# Sheet2.net
KiCad netlist of a schematic drawn in Altium Designer
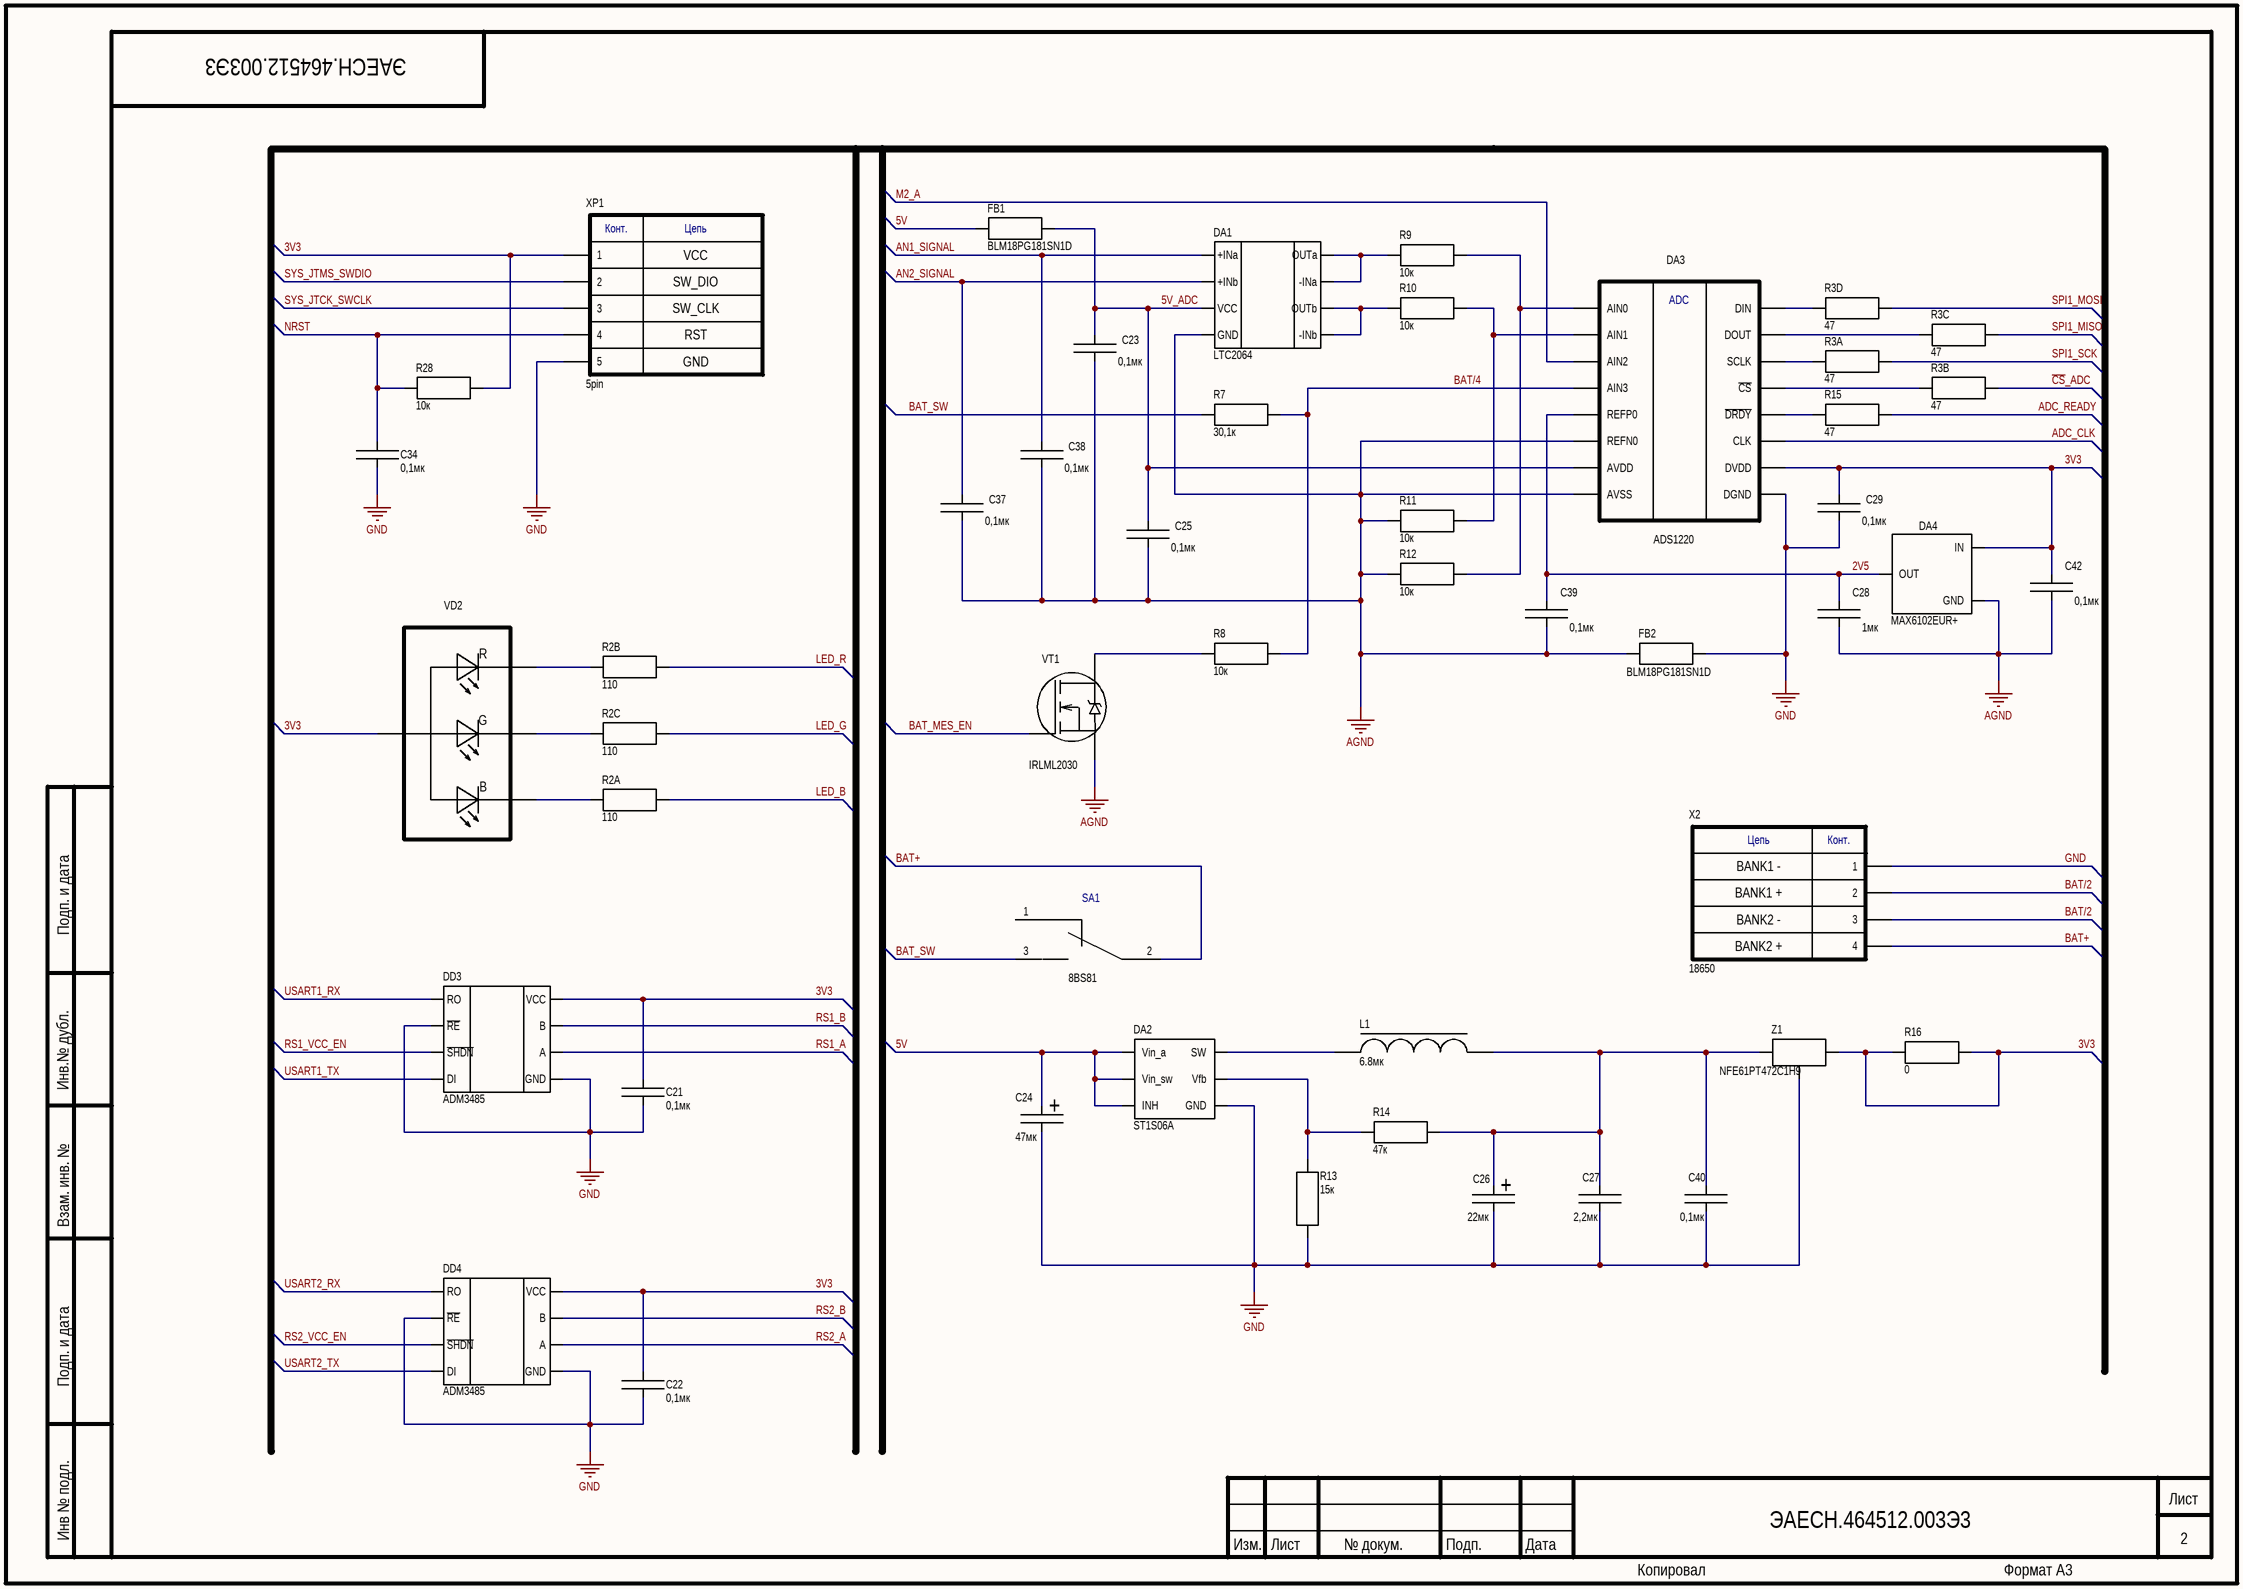
[diagram p0: Sheet2.SchDoc]

(export (version "E")
  (design (tool "Eeschema 10.0.6"))
  (components
    (comp (ref "C21")
      (value "0,1мк")
      (footprint "С0603")
      (fields (field (name "Comment") "C"))
      (libsource (lib "Schlib1") (part "C"))
    )
    (comp (ref "C22")
      (value "0,1мк")
      (footprint "С0603")
      (fields (field (name "Comment") "C"))
      (libsource (lib "Schlib1") (part "C"))
    )
    (comp (ref "C23")
      (value "0,1мк")
      (footprint "С0603")
      (fields (field (name "Comment") "C"))
      (libsource (lib "Schlib1") (part "C"))
    )
    (comp (ref "C24")
      (value "47мк")
      (footprint "CASE B")
      (fields (field (name "Comment") "C_el"))
      (libsource (lib "Schlib1") (part "C_el"))
    )
    (comp (ref "C25")
      (value "0,1мк")
      (footprint "С0603")
      (fields (field (name "Comment") "C"))
      (libsource (lib "Schlib1") (part "C"))
    )
    (comp (ref "C26")
      (value "22мк")
      (footprint "Case A")
      (fields (field (name "Comment") "C_el"))
      (libsource (lib "Schlib1") (part "C_el"))
    )
    (comp (ref "C27")
      (value "2,2мк")
      (footprint "С0603")
      (fields (field (name "Comment") "C"))
      (libsource (lib "Schlib1") (part "C"))
    )
    (comp (ref "C28")
      (value "1мк")
      (footprint "С0603")
      (fields (field (name "Comment") "C"))
      (libsource (lib "Schlib1") (part "C"))
    )
    (comp (ref "C29")
      (value "0,1мк")
      (footprint "С0603")
      (fields (field (name "Comment") "C"))
      (libsource (lib "Schlib1") (part "C"))
    )
    (comp (ref "C34")
      (value "0,1мк")
      (footprint "С0603")
      (fields (field (name "Comment") "C"))
      (libsource (lib "Schlib1") (part "C"))
    )
    (comp (ref "C37")
      (value "0,1мк")
      (footprint "С0603")
      (fields (field (name "Comment") "C"))
      (libsource (lib "Schlib1") (part "C"))
    )
    (comp (ref "C38")
      (value "0,1мк")
      (footprint "С0603")
      (fields (field (name "Comment") "C"))
      (libsource (lib "Schlib1") (part "C"))
    )
    (comp (ref "C39")
      (value "0,1мк")
      (footprint "С0603")
      (fields (field (name "Comment") "C"))
      (libsource (lib "Schlib1") (part "C"))
    )
    (comp (ref "C40")
      (value "0,1мк")
      (footprint "С0603")
      (fields (field (name "Comment") "C"))
      (libsource (lib "Schlib1") (part "C"))
    )
    (comp (ref "C42")
      (value "0,1мк")
      (footprint "С0603")
      (fields (field (name "Comment") "C"))
      (libsource (lib "Schlib1") (part "C"))
    )
    (comp (ref "DA1") (value "LTC2064") (footprint "MSOP8") (libsource (lib "Schlib1") (part "LTC2064")))
    (comp (ref "DA2") (value "ST1S06A") (footprint "DFN6") (libsource (lib "Schlib1") (part "ST1S06A")))
    (comp (ref "DA3") (value "ADS1220") (footprint "TSSOP-16") (libsource (lib "Schlib1") (part "ADC1220")))
    (comp (ref "DA4")
      (value "MAX6102EUR+")
      (footprint "SOT-23")
      (libsource (lib "Schlib1") (part "MAX6102EUR+"))
    )
    (comp (ref "DD3")
      (value "ADM3485")
      (footprint "SOIC8")
      (description "RS485")
      (libsource (lib "Schlib1") (part "MAX13487"))
    )
    (comp (ref "DD4")
      (value "ADM3485")
      (footprint "SOIC8")
      (description "RS485")
      (libsource (lib "Schlib1") (part "MAX13487"))
    )
    (comp (ref "FB1") (value "BLM18PG181SN1D") (footprint "R0603") (libsource (lib "Schlib1") (part "R")))
    (comp (ref "FB2") (value "BLM18PG181SN1D") (footprint "R0603") (libsource (lib "Schlib1") (part "R")))
    (comp (ref "L1") (value "6.8мк") (footprint "Ind_6.5x6.5") (libsource (lib "Schlib1") (part "L")))
    (comp (ref "R2")
      (value "110")
      (footprint "CAT16")
      (fields (field (name "Comment") "RES_4"))
      (libsource (lib "Schlib1") (part "RES_4"))
    )
    (comp (ref "R3")
      (value "47")
      (footprint "CAT16")
      (fields (field (name "Comment") "RES_4"))
      (libsource (lib "Schlib1") (part "RES_4"))
    )
    (comp (ref "R7")
      (value "30,1к")
      (footprint "R0603")
      (fields (field (name "Comment") "R"))
      (libsource (lib "Schlib1") (part "R"))
    )
    (comp (ref "R8")
      (value "10к")
      (footprint "R0603")
      (fields (field (name "Comment") "R"))
      (libsource (lib "Schlib1") (part "R"))
    )
    (comp (ref "R9")
      (value "10к")
      (footprint "R0603")
      (fields (field (name "Comment") "R"))
      (libsource (lib "Schlib1") (part "R"))
    )
    (comp (ref "R10")
      (value "10к")
      (footprint "R0603")
      (fields (field (name "Comment") "R"))
      (libsource (lib "Schlib1") (part "R"))
    )
    (comp (ref "R11")
      (value "10к")
      (footprint "R0603")
      (fields (field (name "Comment") "R"))
      (libsource (lib "Schlib1") (part "R"))
    )
    (comp (ref "R12")
      (value "10к")
      (footprint "R0603")
      (fields (field (name "Comment") "R"))
      (libsource (lib "Schlib1") (part "R"))
    )
    (comp (ref "R13")
      (value "15к")
      (footprint "R0603")
      (fields (field (name "Comment") "R"))
      (libsource (lib "Schlib1") (part "R"))
    )
    (comp (ref "R14")
      (value "47к")
      (footprint "R0603")
      (fields (field (name "Comment") "R"))
      (libsource (lib "Schlib1") (part "R"))
    )
    (comp (ref "R15")
      (value "47")
      (footprint "R0603")
      (fields (field (name "Comment") "R"))
      (libsource (lib "Schlib1") (part "R"))
    )
    (comp (ref "R16")
      (value "0")
      (footprint "R1206")
      (fields (field (name "Comment") "R"))
      (libsource (lib "Schlib1") (part "R"))
    )
    (comp (ref "R28")
      (value "10к")
      (footprint "R0603")
      (fields (field (name "Comment") "R"))
      (libsource (lib "Schlib1") (part "R"))
    )
    (comp (ref "SA1") (value "8BS81") (footprint "SMTS-102") (libsource (lib "Schlib1") (part "Button")))
    (comp (ref "VD2")
      (value "FYLS-3528RGBC")
      (footprint "LED_RGB")
      (libsource (lib "Schlib1") (part "LED_RGB"))
    )
    (comp (ref "VT1") (value "IRLML2030") (footprint "SOT-23") (libsource (lib "Schlib1") (part "N-channel")))
    (comp (ref "X2")
      (value "18650")
      (footprint "18650_holder")
      (libsource (lib "Schlib1") (part "18650_holder"))
    )
    (comp (ref "XP1") (value "5pin") (footprint "PLS-5") (libsource (lib "Schlib1") (part "5pin")))
    (comp (ref "Z1")
      (value "NFE61PT472C1H9")
      (footprint "NFE61P")
      (libsource (lib "Schlib1") (part "Filter"))
    )
  )
  (nets
    (net (code "1") (name "/2V5") (class "Default")
      (node (ref "C28") (pin "1") (pinfunction "1_1") (pintype "passive"))
      (node (ref "C39") (pin "1") (pinfunction "1_1") (pintype "passive"))
      (node (ref "DA3") (pin "9") (pinfunction "REFP0_9") (pintype "passive"))
      (node (ref "DA4") (pin "2") (pinfunction "OUT_2") (pintype "passive"))
    )
    (net (code "2") (name "/3V3") (class "Default")
      (node (ref "C21") (pin "1") (pinfunction "1_1") (pintype "passive"))
      (node (ref "C22") (pin "1") (pinfunction "1_1") (pintype "passive"))
      (node (ref "C29") (pin "1") (pinfunction "1_1") (pintype "passive"))
      (node (ref "C42") (pin "1") (pinfunction "1_1") (pintype "passive"))
      (node (ref "DA3") (pin "13") (pinfunction "DVDD_13") (pintype "passive"))
      (node (ref "DA4") (pin "1") (pinfunction "IN_1") (pintype "passive"))
      (node (ref "DD3") (pin "8") (pinfunction "VCC_8") (pintype "passive"))
      (node (ref "DD4") (pin "8") (pinfunction "VCC_8") (pintype "passive"))
      (node (ref "R16") (pin "1") (pinfunction "1_1") (pintype "passive"))
      (node (ref "R16") (pin "2") (pinfunction "2_2") (pintype "passive"))
      (node (ref "R28") (pin "2") (pinfunction "2_2") (pintype "passive"))
      (node (ref "VD2") (pin "2") (pinfunction "2_2") (pintype "passive"))
      (node (ref "XP1") (pin "1") (pinfunction "1_1") (pintype "passive"))
      (node (ref "Z1") (pin "2") (pinfunction "2_2") (pintype "passive"))
    )
    (net (code "3") (name "/5V") (class "Default")
      (node (ref "C24") (pin "1") (pinfunction "1_1") (pintype "passive"))
      (node (ref "DA2") (pin "4") (pinfunction "Vin_sw_4") (pintype "passive"))
      (node (ref "DA2") (pin "5") (pinfunction "Vin_a_5") (pintype "passive"))
      (node (ref "DA2") (pin "6") (pinfunction "INH_6") (pintype "passive"))
      (node (ref "FB1") (pin "2") (pinfunction "2_2") (pintype "passive"))
    )
    (net (code "4") (name "/5V_ADC") (class "Default")
      (node (ref "C23") (pin "1") (pinfunction "1_1") (pintype "passive"))
      (node (ref "C25") (pin "1") (pinfunction "1_1") (pintype "passive"))
      (node (ref "DA1") (pin "8") (pinfunction "VCC_8") (pintype "passive"))
      (node (ref "DA3") (pin "12") (pinfunction "AVDD_12") (pintype "passive"))
      (node (ref "FB1") (pin "1") (pinfunction "1_1") (pintype "passive"))
    )
    (net (code "5") (name "/ADC_CLK") (class "Default")
      (node (ref "DA3") (pin "3") (pinfunction "CLK_3") (pintype "passive"))
    )
    (net (code "6") (name "/ADC_READY") (class "Default")
      (node (ref "R15") (pin "2") (pinfunction "2_2") (pintype "passive"))
    )
    (net (code "7") (name "/AN1_SIGNAL") (class "Default")
      (node (ref "C38") (pin "1") (pinfunction "1_1") (pintype "passive"))
      (node (ref "DA1") (pin "3") (pinfunction "+INa_3") (pintype "passive"))
    )
    (net (code "8") (name "/AN2_SIGNAL") (class "Default")
      (node (ref "C37") (pin "1") (pinfunction "1_1") (pintype "passive"))
      (node (ref "DA1") (pin "5") (pinfunction "+INb_5") (pintype "passive"))
    )
    (net (code "9") (name "/BAT+") (class "Default")
      (node (ref "SA1") (pin "2") (pintype "passive"))
      (node (ref "X2") (pin "4") (pinfunction "4_4") (pintype "passive"))
    )
    (net (code "10") (name "/BAT_MES_EN") (class "Default")
      (node (ref "VT1") (pin "1") (pinfunction "G_1") (pintype "passive"))
    )
    (net (code "11") (name "/BAT_SW") (class "Default")
      (node (ref "R7") (pin "1") (pinfunction "1_1") (pintype "passive"))
      (node (ref "SA1") (pin "3") (pintype "passive"))
    )
    (net (code "12") (name "/BAT{slash}2") (class "Default")
      (node (ref "X2") (pin "2") (pinfunction "2_2") (pintype "passive"))
      (node (ref "X2") (pin "3") (pinfunction "3_3") (pintype "passive"))
    )
    (net (code "13") (name "/BAT{slash}4") (class "Default")
      (node (ref "DA3") (pin "6") (pinfunction "AIN3_6") (pintype "passive"))
      (node (ref "R7") (pin "2") (pinfunction "2_2") (pintype "passive"))
      (node (ref "R8") (pin "2") (pinfunction "2_2") (pintype "passive"))
    )
    (net (code "14") (name "/LED_B") (class "Default")
      (node (ref "R2") (pin "8") (pinfunction "8_8") (pintype "passive"))
    )
    (net (code "15") (name "/LED_G") (class "Default")
      (node (ref "R2") (pin "6") (pinfunction "6_6") (pintype "passive"))
    )
    (net (code "16") (name "/LED_R") (class "Default")
      (node (ref "R2") (pin "7") (pinfunction "7_7") (pintype "passive"))
    )
    (net (code "17") (name "/M2_A") (class "Default")
      (node (ref "DA3") (pin "7") (pinfunction "AIN2_7") (pintype "passive"))
    )
    (net (code "18") (name "/NRST") (class "Default")
      (node (ref "C34") (pin "1") (pinfunction "1_1") (pintype "passive"))
      (node (ref "R28") (pin "1") (pinfunction "1_1") (pintype "passive"))
      (node (ref "XP1") (pin "4") (pinfunction "4_4") (pintype "passive"))
    )
    (net (code "19") (name "/RS1_A") (class "Default")
      (node (ref "DD3") (pin "6") (pinfunction "A_6") (pintype "passive"))
    )
    (net (code "20") (name "/RS1_B") (class "Default")
      (node (ref "DD3") (pin "7") (pinfunction "B_7") (pintype "passive"))
    )
    (net (code "21") (name "/RS1_VCC_EN") (class "Default")
      (node (ref "DD3") (pin "3") (pinfunction "~{SHDN}_3") (pintype "passive"))
    )
    (net (code "22") (name "/RS2_A") (class "Default")
      (node (ref "DD4") (pin "6") (pinfunction "A_6") (pintype "passive"))
    )
    (net (code "23") (name "/RS2_B") (class "Default")
      (node (ref "DD4") (pin "7") (pinfunction "B_7") (pintype "passive"))
    )
    (net (code "24") (name "/RS2_VCC_EN") (class "Default")
      (node (ref "DD4") (pin "3") (pinfunction "~{SHDN}_3") (pintype "passive"))
    )
    (net (code "25") (name "/SPI1_MISO") (class "Default")
      (node (ref "R3") (pin "6") (pinfunction "6_6") (pintype "passive"))
    )
    (net (code "26") (name "/SPI1_MOSI") (class "Default")
      (node (ref "R3") (pin "5") (pinfunction "5_5") (pintype "passive"))
    )
    (net (code "27") (name "/SPI1_SCK") (class "Default")
      (node (ref "R3") (pin "8") (pinfunction "8_8") (pintype "passive"))
    )
    (net (code "28") (name "/SYS_JTCK_SWCLK") (class "Default")
      (node (ref "XP1") (pin "3") (pinfunction "3_3") (pintype "passive"))
    )
    (net (code "29") (name "/SYS_JTMS_SWDIO") (class "Default")
      (node (ref "XP1") (pin "2") (pinfunction "2_2") (pintype "passive"))
    )
    (net (code "30") (name "/USART1_RX") (class "Default")
      (node (ref "DD3") (pin "1") (pinfunction "RO_1") (pintype "passive"))
    )
    (net (code "31") (name "/USART1_TX") (class "Default")
      (node (ref "DD3") (pin "4") (pinfunction "DI_4") (pintype "passive"))
    )
    (net (code "32") (name "/USART2_RX") (class "Default")
      (node (ref "DD4") (pin "1") (pinfunction "RO_1") (pintype "passive"))
    )
    (net (code "33") (name "/USART2_TX") (class "Default")
      (node (ref "DD4") (pin "4") (pinfunction "DI_4") (pintype "passive"))
    )
    (net (code "34") (name "/~{CS}_ADC") (class "Default")
      (node (ref "R3") (pin "7") (pinfunction "7_7") (pintype "passive"))
    )
    (net (code "35") (name "AGND") (class "Default")
      (node (ref "C23") (pin "2") (pinfunction "2_2") (pintype "passive"))
      (node (ref "C25") (pin "2") (pinfunction "2_2") (pintype "passive"))
      (node (ref "C28") (pin "2") (pinfunction "2_2") (pintype "passive"))
      (node (ref "C37") (pin "2") (pinfunction "2_2") (pintype "passive"))
      (node (ref "C38") (pin "2") (pinfunction "2_2") (pintype "passive"))
      (node (ref "C39") (pin "2") (pinfunction "2_2") (pintype "passive"))
      (node (ref "C42") (pin "2") (pinfunction "2_2") (pintype "passive"))
      (node (ref "DA1") (pin "4") (pinfunction "GND_4") (pintype "passive"))
      (node (ref "DA3") (pin "5") (pinfunction "AVSS_5") (pintype "passive"))
      (node (ref "DA3") (pin "8") (pinfunction "REFN0_8") (pintype "passive"))
      (node (ref "DA4") (pin "3") (pinfunction "GND_3") (pintype "passive"))
      (node (ref "FB2") (pin "1") (pinfunction "1_1") (pintype "passive"))
      (node (ref "R11") (pin "2") (pinfunction "2_2") (pintype "passive"))
      (node (ref "R12") (pin "2") (pinfunction "2_2") (pintype "passive"))
      (node (ref "VT1") (pin "2") (pinfunction "S_2") (pintype "passive"))
    )
    (net (code "36") (name "GND") (class "Default")
      (node (ref "C21") (pin "2") (pinfunction "2_2") (pintype "passive"))
      (node (ref "C22") (pin "2") (pinfunction "2_2") (pintype "passive"))
      (node (ref "C24") (pin "2") (pinfunction "2_2") (pintype "passive"))
      (node (ref "C26") (pin "2") (pinfunction "2_2") (pintype "passive"))
      (node (ref "C27") (pin "2") (pinfunction "2_2") (pintype "passive"))
      (node (ref "C29") (pin "2") (pinfunction "2_2") (pintype "passive"))
      (node (ref "C34") (pin "2") (pinfunction "2_2") (pintype "passive"))
      (node (ref "C40") (pin "2") (pinfunction "2_2") (pintype "passive"))
      (node (ref "DA2") (pin "2") (pinfunction "GND_2") (pintype "passive"))
      (node (ref "DA3") (pin "4") (pinfunction "DGND_4") (pintype "passive"))
      (node (ref "DD3") (pin "2") (pinfunction "~{RE}_2") (pintype "passive"))
      (node (ref "DD3") (pin "5") (pinfunction "GND_5") (pintype "passive"))
      (node (ref "DD4") (pin "2") (pinfunction "~{RE}_2") (pintype "passive"))
      (node (ref "DD4") (pin "5") (pinfunction "GND_5") (pintype "passive"))
      (node (ref "FB2") (pin "2") (pinfunction "2_2") (pintype "passive"))
      (node (ref "R13") (pin "1") (pinfunction "1_1") (pintype "passive"))
      (node (ref "X2") (pin "1") (pinfunction "1_1") (pintype "passive"))
      (node (ref "XP1") (pin "5") (pinfunction "5_5") (pintype "passive"))
      (node (ref "Z1") (pin "3") (pinfunction "GND_3") (pintype "passive"))
    )
    (net (code "37") (name "Net-(C26-Pad1)") (class "Default")
      (node (ref "C26") (pin "1") (pinfunction "1_1") (pintype "passive"))
      (node (ref "C27") (pin "1") (pinfunction "1_1") (pintype "passive"))
      (node (ref "C40") (pin "1") (pinfunction "1_1") (pintype "passive"))
      (node (ref "L1") (pin "1") (pinfunction "1_1") (pintype "passive"))
      (node (ref "R14") (pin "2") (pinfunction "2_2") (pintype "passive"))
      (node (ref "Z1") (pin "1") (pinfunction "1_1") (pintype "passive"))
    )
    (net (code "38") (name "Net-(DA1--INa)") (class "Default")
      (node (ref "DA1") (pin "1") (pinfunction "OUTa_1") (pintype "passive"))
      (node (ref "DA1") (pin "2") (pinfunction "-INa_2") (pintype "passive"))
      (node (ref "R9") (pin "1") (pinfunction "1_1") (pintype "passive"))
    )
    (net (code "39") (name "Net-(DA1--INb)") (class "Default")
      (node (ref "DA1") (pin "6") (pinfunction "-INb_6") (pintype "passive"))
      (node (ref "DA1") (pin "7") (pinfunction "OUTb_7") (pintype "passive"))
      (node (ref "R10") (pin "1") (pinfunction "1_1") (pintype "passive"))
    )
    (net (code "40") (name "Net-(DA2-SW)") (class "Default")
      (node (ref "DA2") (pin "3") (pinfunction "SW_3") (pintype "passive"))
      (node (ref "L1") (pin "2") (pinfunction "2_2") (pintype "passive"))
    )
    (net (code "41") (name "Net-(DA2-Vfb)") (class "Default")
      (node (ref "DA2") (pin "1") (pinfunction "Vfb_1") (pintype "passive"))
      (node (ref "R13") (pin "2") (pinfunction "2_2") (pintype "passive"))
      (node (ref "R14") (pin "1") (pinfunction "1_1") (pintype "passive"))
    )
    (net (code "42") (name "Net-(DA3-AIN0)") (class "Default")
      (node (ref "DA3") (pin "11") (pinfunction "AIN0_11") (pintype "passive"))
      (node (ref "R12") (pin "1") (pinfunction "1_1") (pintype "passive"))
      (node (ref "R9") (pin "2") (pinfunction "2_2") (pintype "passive"))
    )
    (net (code "43") (name "Net-(DA3-AIN1)") (class "Default")
      (node (ref "DA3") (pin "10") (pinfunction "AIN1_10") (pintype "passive"))
      (node (ref "R10") (pin "2") (pinfunction "2_2") (pintype "passive"))
      (node (ref "R11") (pin "1") (pinfunction "1_1") (pintype "passive"))
    )
    (net (code "44") (name "Net-(DA3-DIN)") (class "Default")
      (node (ref "DA3") (pin "16") (pinfunction "DIN_16") (pintype "passive"))
      (node (ref "R3") (pin "4") (pinfunction "4_4") (pintype "passive"))
    )
    (net (code "45") (name "Net-(DA3-DOUT)") (class "Default")
      (node (ref "DA3") (pin "15") (pinfunction "DOUT_15") (pintype "passive"))
      (node (ref "R3") (pin "3") (pinfunction "3_3") (pintype "passive"))
    )
    (net (code "46") (name "Net-(DA3-SCLK)") (class "Default")
      (node (ref "DA3") (pin "1") (pinfunction "SCLK_1") (pintype "passive"))
      (node (ref "R3") (pin "1") (pinfunction "1_1") (pintype "passive"))
    )
    (net (code "47") (name "Net-(DA3-~{CS})") (class "Default")
      (node (ref "DA3") (pin "2") (pinfunction "~{CS}_2") (pintype "passive"))
      (node (ref "R3") (pin "2") (pinfunction "2_2") (pintype "passive"))
    )
    (net (code "48") (name "Net-(DA3-~{DRDY})") (class "Default")
      (node (ref "DA3") (pin "14") (pinfunction "~{DRDY}_14") (pintype "passive"))
      (node (ref "R15") (pin "1") (pinfunction "1_1") (pintype "passive"))
    )
    (net (code "49") (name "Net-(R2-Pad1)") (class "Default")
      (node (ref "R2") (pin "1") (pinfunction "1_1") (pintype "passive"))
      (node (ref "VD2") (pin "3") (pinfunction "3_3") (pintype "passive"))
    )
    (net (code "50") (name "Net-(R2-Pad2)") (class "Default")
      (node (ref "R2") (pin "2") (pinfunction "2_2") (pintype "passive"))
      (node (ref "VD2") (pin "1") (pinfunction "1_1") (pintype "passive"))
    )
    (net (code "51") (name "Net-(R2-Pad3)") (class "Default")
      (node (ref "R2") (pin "3") (pinfunction "3_3") (pintype "passive"))
      (node (ref "VD2") (pin "4") (pinfunction "4_4") (pintype "passive"))
    )
    (net (code "52") (name "Net-(VT1-D)") (class "Default")
      (node (ref "R8") (pin "1") (pinfunction "1_1") (pintype "passive"))
      (node (ref "VT1") (pin "3") (pinfunction "D_3") (pintype "passive"))
    )
    (net (code "53") (name "unconnected-(SA1-Pad1)") (class "Default")
      (node (ref "SA1") (pin "1") (pintype "passive"))
    )
  )
)
